# server.net
KiCad netlist of a schematic drawn in EAGLE
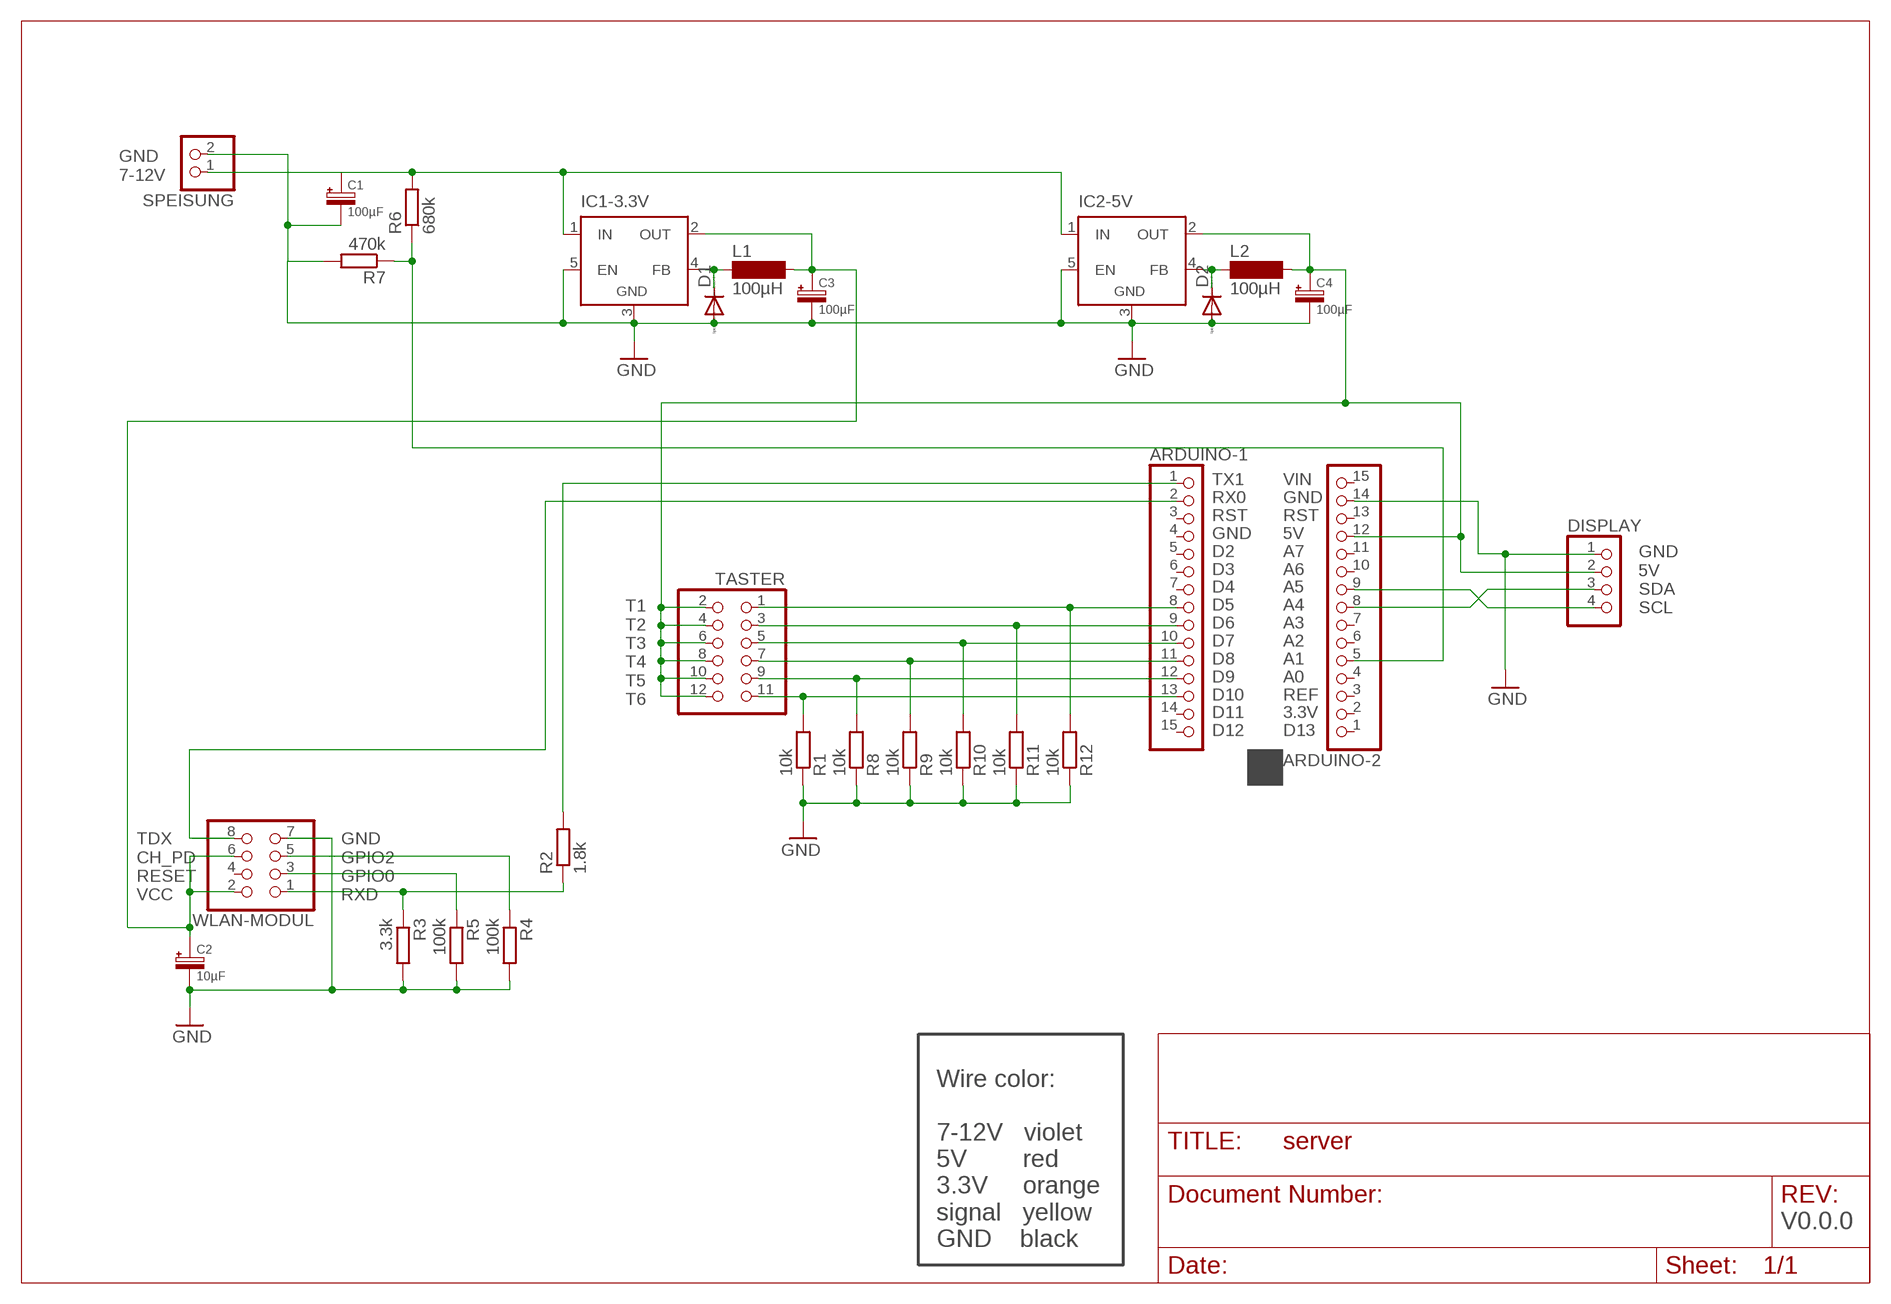
[diagram p0: schematic, sheet 1]

(export (version "E")
  (design (tool "Eeschema 10.0.6"))
  (components
    (comp (ref "ARDUINO-1")
      (value "PINHD-1X15")
      (footprint "eagle-import:1X15")
      (libsource (lib "eagle-import") (part "PINHD-1X15"))
    )
    (comp (ref "ARDUINO-2")
      (value "PINHD-1X15")
      (footprint "eagle-import:1X15")
      (libsource (lib "eagle-import") (part "PINHD-1X15"))
    )
    (comp (ref "C1")
      (value "100µF")
      (footprint "eagle-import:KONDENSATOR_ELEKTROLYT")
      (libsource (lib "eagle-import") (part "KONDENSATOR_ELEKTROLYT"))
    )
    (comp (ref "C2")
      (value "10µF")
      (footprint "eagle-import:KONDENSATOR_ELEKTROLYT")
      (libsource (lib "eagle-import") (part "KONDENSATOR_ELEKTROLYT"))
    )
    (comp (ref "C3")
      (value "100µF")
      (footprint "eagle-import:KONDENSATOR_ELEKTROLYT")
      (libsource (lib "eagle-import") (part "KONDENSATOR_ELEKTROLYT"))
    )
    (comp (ref "C4")
      (value "100µF")
      (footprint "eagle-import:KONDENSATOR_ELEKTROLYT")
      (libsource (lib "eagle-import") (part "KONDENSATOR_ELEKTROLYT"))
    )
    (comp (ref "D1")
      (value "DIODE-D-2.5")
      (footprint "eagle-import:D-2.5")
      (libsource (lib "eagle-import") (part "DIODE-D-2.5"))
    )
    (comp (ref "D2")
      (value "DIODE-D-2.5")
      (footprint "eagle-import:D-2.5")
      (libsource (lib "eagle-import") (part "DIODE-D-2.5"))
    )
    (comp (ref "DISPLAY")
      (value "PINHD-1X4")
      (footprint "eagle-import:1X04")
      (libsource (lib "eagle-import") (part "PINHD-1X4"))
    )
    (comp (ref "IC1-3.3V")
      (value "LM2596TV")
      (footprint "eagle-import:TO220-51")
      (libsource (lib "eagle-import") (part "LM2596TV"))
    )
    (comp (ref "IC2-5V")
      (value "LM2596TV")
      (footprint "eagle-import:TO220-51")
      (libsource (lib "eagle-import") (part "LM2596TV"))
    )
    (comp (ref "L1")
      (value "100µH")
      (footprint "eagle-import:SM-L15A")
      (libsource (lib "eagle-import") (part "SM-L15A"))
    )
    (comp (ref "L2")
      (value "100µH")
      (footprint "eagle-import:SM-L15A")
      (libsource (lib "eagle-import") (part "SM-L15A"))
    )
    (comp (ref "R1")
      (value "10k")
      (footprint "eagle-import:0207_15")
      (libsource (lib "eagle-import") (part "rcl_334_R-EU_0207/15"))
    )
    (comp (ref "R2")
      (value "1.8k")
      (footprint "eagle-import:0207_10")
      (libsource (lib "eagle-import") (part "R-EU_0207/10"))
    )
    (comp (ref "R3")
      (value "3.3k")
      (footprint "eagle-import:0207_10")
      (libsource (lib "eagle-import") (part "R-EU_0207/10"))
    )
    (comp (ref "R4")
      (value "100k")
      (footprint "eagle-import:0207_10")
      (libsource (lib "eagle-import") (part "R-EU_0207/10"))
    )
    (comp (ref "R5")
      (value "100k")
      (footprint "eagle-import:0207_10")
      (libsource (lib "eagle-import") (part "R-EU_0207/10"))
    )
    (comp (ref "R6")
      (value "680k")
      (footprint "eagle-import:0204V")
      (libsource (lib "eagle-import") (part "rcl_334_R-EU_0204/2V"))
    )
    (comp (ref "R7")
      (value "470k")
      (footprint "eagle-import:0204V")
      (libsource (lib "eagle-import") (part "rcl_334_R-EU_0204/2V"))
    )
    (comp (ref "R8")
      (value "10k")
      (footprint "eagle-import:0207_12")
      (libsource (lib "eagle-import") (part "rcl_334_R-EU_0207/12"))
    )
    (comp (ref "R9")
      (value "10k")
      (footprint "eagle-import:0207_10")
      (libsource (lib "eagle-import") (part "rcl_334_R-EU_0207/10"))
    )
    (comp (ref "R10")
      (value "10k")
      (footprint "eagle-import:0207_7")
      (libsource (lib "eagle-import") (part "rcl_334_R-EU_0207/7"))
    )
    (comp (ref "R11")
      (value "10k")
      (footprint "eagle-import:0207_5V")
      (libsource (lib "eagle-import") (part "rcl_334_R-EU_0207/5V"))
    )
    (comp (ref "R12")
      (value "10k")
      (footprint "eagle-import:0207_2V")
      (libsource (lib "eagle-import") (part "rcl_334_R-EU_0207/2V"))
    )
    (comp (ref "SPEISUNG")
      (value "PINHD-1X2")
      (footprint "eagle-import:1X02")
      (libsource (lib "eagle-import") (part "PINHD-1X2"))
    )
    (comp (ref "TASTER")
      (value "PINHD-2X6")
      (footprint "eagle-import:2X06")
      (libsource (lib "eagle-import") (part "PINHD-2X6"))
    )
    (comp (ref "WLAN-MODUL")
      (value "PINHD-2X4")
      (footprint "eagle-import:2X04")
      (libsource (lib "eagle-import") (part "PINHD-2X4"))
    )
  )
  (nets
    (net (code "1") (name "GND") (class "Default")
      (node (ref "ARDUINO-2") (pin "14") (pinfunction "14_14") (pintype "passive"))
      (node (ref "C1") (pin "P$1") (pinfunction "P$1_P$1") (pintype "passive"))
      (node (ref "C2") (pin "P$1") (pinfunction "P$1_P$1") (pintype "passive"))
      (node (ref "C3") (pin "P$1") (pinfunction "P$1_P$1") (pintype "passive"))
      (node (ref "C4") (pin "P$1") (pinfunction "P$1_P$1") (pintype "passive"))
      (node (ref "D1") (pin "A") (pinfunction "A_A") (pintype "passive"))
      (node (ref "D2") (pin "A") (pinfunction "A_A") (pintype "passive"))
      (node (ref "DISPLAY") (pin "1") (pinfunction "1_1") (pintype "passive"))
      (node (ref "IC1-3.3V") (pin "3") (pinfunction "GND_3") (pintype "power_in"))
      (node (ref "IC1-3.3V") (pin "5") (pinfunction "EN_5") (pintype "input"))
      (node (ref "IC2-5V") (pin "3") (pinfunction "GND_3") (pintype "power_in"))
      (node (ref "IC2-5V") (pin "5") (pinfunction "EN_5") (pintype "input"))
      (node (ref "R1") (pin "1") (pinfunction "1_1") (pintype "passive"))
      (node (ref "R10") (pin "1") (pinfunction "1_1") (pintype "passive"))
      (node (ref "R11") (pin "1") (pinfunction "1_1") (pintype "passive"))
      (node (ref "R12") (pin "1") (pinfunction "1_1") (pintype "passive"))
      (node (ref "R3") (pin "2") (pinfunction "2_2") (pintype "passive"))
      (node (ref "R4") (pin "2") (pinfunction "2_2") (pintype "passive"))
      (node (ref "R5") (pin "2") (pinfunction "2_2") (pintype "passive"))
      (node (ref "R7") (pin "2") (pinfunction "2_2") (pintype "passive"))
      (node (ref "R8") (pin "1") (pinfunction "1_1") (pintype "passive"))
      (node (ref "R9") (pin "1") (pinfunction "1_1") (pintype "passive"))
      (node (ref "SPEISUNG") (pin "2") (pinfunction "2_2") (pintype "passive"))
      (node (ref "WLAN-MODUL") (pin "7") (pinfunction "7_7") (pintype "passive"))
    )
    (net (code "2") (name "Net-(ARDUINO-1-Pad1)") (class "Default")
      (node (ref "ARDUINO-1") (pin "1") (pinfunction "1_1") (pintype "passive"))
      (node (ref "R2") (pin "2") (pinfunction "2_2") (pintype "passive"))
    )
    (net (code "3") (name "Net-(ARDUINO-1-Pad2)") (class "Default")
      (node (ref "ARDUINO-1") (pin "2") (pinfunction "2_2") (pintype "passive"))
      (node (ref "WLAN-MODUL") (pin "8") (pinfunction "8_8") (pintype "passive"))
    )
    (net (code "4") (name "Net-(ARDUINO-1-Pad8)") (class "Default")
      (node (ref "ARDUINO-1") (pin "8") (pinfunction "8_8") (pintype "passive"))
      (node (ref "R12") (pin "2") (pinfunction "2_2") (pintype "passive"))
      (node (ref "TASTER") (pin "1") (pinfunction "1_1") (pintype "passive"))
    )
    (net (code "5") (name "Net-(ARDUINO-1-Pad9)") (class "Default")
      (node (ref "ARDUINO-1") (pin "9") (pinfunction "9_9") (pintype "passive"))
      (node (ref "R11") (pin "2") (pinfunction "2_2") (pintype "passive"))
      (node (ref "TASTER") (pin "3") (pinfunction "3_3") (pintype "passive"))
    )
    (net (code "6") (name "Net-(ARDUINO-1-Pad10)") (class "Default")
      (node (ref "ARDUINO-1") (pin "10") (pinfunction "10_10") (pintype "passive"))
      (node (ref "R10") (pin "2") (pinfunction "2_2") (pintype "passive"))
      (node (ref "TASTER") (pin "5") (pinfunction "5_5") (pintype "passive"))
    )
    (net (code "7") (name "Net-(ARDUINO-1-Pad11)") (class "Default")
      (node (ref "ARDUINO-1") (pin "11") (pinfunction "11_11") (pintype "passive"))
      (node (ref "R9") (pin "2") (pinfunction "2_2") (pintype "passive"))
      (node (ref "TASTER") (pin "7") (pinfunction "7_7") (pintype "passive"))
    )
    (net (code "8") (name "Net-(ARDUINO-1-Pad12)") (class "Default")
      (node (ref "ARDUINO-1") (pin "12") (pinfunction "12_12") (pintype "passive"))
      (node (ref "R8") (pin "2") (pinfunction "2_2") (pintype "passive"))
      (node (ref "TASTER") (pin "9") (pinfunction "9_9") (pintype "passive"))
    )
    (net (code "9") (name "Net-(ARDUINO-1-Pad13)") (class "Default")
      (node (ref "ARDUINO-1") (pin "13") (pinfunction "13_13") (pintype "passive"))
      (node (ref "R1") (pin "2") (pinfunction "2_2") (pintype "passive"))
      (node (ref "TASTER") (pin "11") (pinfunction "11_11") (pintype "passive"))
    )
    (net (code "10") (name "Net-(ARDUINO-2-Pad5)") (class "Default")
      (node (ref "ARDUINO-2") (pin "5") (pinfunction "5_5") (pintype "passive"))
      (node (ref "R6") (pin "1") (pinfunction "1_1") (pintype "passive"))
      (node (ref "R7") (pin "1") (pinfunction "1_1") (pintype "passive"))
    )
    (net (code "11") (name "Net-(ARDUINO-2-Pad8)") (class "Default")
      (node (ref "ARDUINO-2") (pin "8") (pinfunction "8_8") (pintype "passive"))
      (node (ref "DISPLAY") (pin "3") (pinfunction "3_3") (pintype "passive"))
    )
    (net (code "12") (name "Net-(ARDUINO-2-Pad9)") (class "Default")
      (node (ref "ARDUINO-2") (pin "9") (pinfunction "9_9") (pintype "passive"))
      (node (ref "DISPLAY") (pin "4") (pinfunction "4_4") (pintype "passive"))
    )
    (net (code "13") (name "Net-(IC1-3.3V-FB)") (class "Default")
      (node (ref "D1") (pin "C") (pinfunction "C_C") (pintype "passive"))
      (node (ref "IC1-3.3V") (pin "4") (pinfunction "FB_4") (pintype "input"))
      (node (ref "L1") (pin "1") (pinfunction "1_1") (pintype "passive"))
    )
    (net (code "14") (name "Net-(IC1-3.3V-IN)") (class "Default")
      (node (ref "C1") (pin "P$2") (pinfunction "P$2_P$2") (pintype "passive"))
      (node (ref "IC1-3.3V") (pin "1") (pinfunction "IN_1") (pintype "input"))
      (node (ref "IC2-5V") (pin "1") (pinfunction "IN_1") (pintype "input"))
      (node (ref "R6") (pin "2") (pinfunction "2_2") (pintype "passive"))
      (node (ref "SPEISUNG") (pin "1") (pinfunction "1_1") (pintype "passive"))
    )
    (net (code "15") (name "Net-(IC1-3.3V-OUT)") (class "Default")
      (node (ref "C2") (pin "P$2") (pinfunction "P$2_P$2") (pintype "passive"))
      (node (ref "C3") (pin "P$2") (pinfunction "P$2_P$2") (pintype "passive"))
      (node (ref "IC1-3.3V") (pin "2") (pinfunction "OUT_2") (pintype "output"))
      (node (ref "L1") (pin "2") (pinfunction "2_2") (pintype "passive"))
      (node (ref "WLAN-MODUL") (pin "2") (pinfunction "2_2") (pintype "passive"))
      (node (ref "WLAN-MODUL") (pin "6") (pinfunction "6_6") (pintype "passive"))
    )
    (net (code "16") (name "Net-(IC2-5V-FB)") (class "Default")
      (node (ref "D2") (pin "C") (pinfunction "C_C") (pintype "passive"))
      (node (ref "IC2-5V") (pin "4") (pinfunction "FB_4") (pintype "input"))
      (node (ref "L2") (pin "1") (pinfunction "1_1") (pintype "passive"))
    )
    (net (code "17") (name "Net-(IC2-5V-OUT)") (class "Default")
      (node (ref "ARDUINO-2") (pin "12") (pinfunction "12_12") (pintype "passive"))
      (node (ref "C4") (pin "P$2") (pinfunction "P$2_P$2") (pintype "passive"))
      (node (ref "DISPLAY") (pin "2") (pinfunction "2_2") (pintype "passive"))
      (node (ref "IC2-5V") (pin "2") (pinfunction "OUT_2") (pintype "output"))
      (node (ref "L2") (pin "2") (pinfunction "2_2") (pintype "passive"))
      (node (ref "TASTER") (pin "10") (pinfunction "10_10") (pintype "passive"))
      (node (ref "TASTER") (pin "12") (pinfunction "12_12") (pintype "passive"))
      (node (ref "TASTER") (pin "2") (pinfunction "2_2") (pintype "passive"))
      (node (ref "TASTER") (pin "4") (pinfunction "4_4") (pintype "passive"))
      (node (ref "TASTER") (pin "6") (pinfunction "6_6") (pintype "passive"))
      (node (ref "TASTER") (pin "8") (pinfunction "8_8") (pintype "passive"))
    )
    (net (code "18") (name "Net-(R2-Pad1)") (class "Default")
      (node (ref "R2") (pin "1") (pinfunction "1_1") (pintype "passive"))
      (node (ref "R3") (pin "1") (pinfunction "1_1") (pintype "passive"))
      (node (ref "WLAN-MODUL") (pin "1") (pinfunction "1_1") (pintype "passive"))
    )
    (net (code "19") (name "Net-(R4-Pad1)") (class "Default")
      (node (ref "R4") (pin "1") (pinfunction "1_1") (pintype "passive"))
      (node (ref "WLAN-MODUL") (pin "5") (pinfunction "5_5") (pintype "passive"))
    )
    (net (code "20") (name "Net-(R5-Pad1)") (class "Default")
      (node (ref "R5") (pin "1") (pinfunction "1_1") (pintype "passive"))
      (node (ref "WLAN-MODUL") (pin "3") (pinfunction "3_3") (pintype "passive"))
    )
    (net (code "21") (name "unconnected-(ARDUINO-1-Pad3)") (class "Default")
      (node (ref "ARDUINO-1") (pin "3") (pinfunction "3_3") (pintype "passive"))
    )
    (net (code "22") (name "unconnected-(ARDUINO-1-Pad4)") (class "Default")
      (node (ref "ARDUINO-1") (pin "4") (pinfunction "4_4") (pintype "passive"))
    )
    (net (code "23") (name "unconnected-(ARDUINO-1-Pad5)") (class "Default")
      (node (ref "ARDUINO-1") (pin "5") (pinfunction "5_5") (pintype "passive"))
    )
    (net (code "24") (name "unconnected-(ARDUINO-1-Pad6)") (class "Default")
      (node (ref "ARDUINO-1") (pin "6") (pinfunction "6_6") (pintype "passive"))
    )
    (net (code "25") (name "unconnected-(ARDUINO-1-Pad7)") (class "Default")
      (node (ref "ARDUINO-1") (pin "7") (pinfunction "7_7") (pintype "passive"))
    )
    (net (code "26") (name "unconnected-(ARDUINO-1-Pad14)") (class "Default")
      (node (ref "ARDUINO-1") (pin "14") (pinfunction "14_14") (pintype "passive"))
    )
    (net (code "27") (name "unconnected-(ARDUINO-1-Pad15)") (class "Default")
      (node (ref "ARDUINO-1") (pin "15") (pinfunction "15_15") (pintype "passive"))
    )
    (net (code "28") (name "unconnected-(ARDUINO-2-Pad1)") (class "Default")
      (node (ref "ARDUINO-2") (pin "1") (pinfunction "1_1") (pintype "passive"))
    )
    (net (code "29") (name "unconnected-(ARDUINO-2-Pad2)") (class "Default")
      (node (ref "ARDUINO-2") (pin "2") (pinfunction "2_2") (pintype "passive"))
    )
    (net (code "30") (name "unconnected-(ARDUINO-2-Pad3)") (class "Default")
      (node (ref "ARDUINO-2") (pin "3") (pinfunction "3_3") (pintype "passive"))
    )
    (net (code "31") (name "unconnected-(ARDUINO-2-Pad4)") (class "Default")
      (node (ref "ARDUINO-2") (pin "4") (pinfunction "4_4") (pintype "passive"))
    )
    (net (code "32") (name "unconnected-(ARDUINO-2-Pad6)") (class "Default")
      (node (ref "ARDUINO-2") (pin "6") (pinfunction "6_6") (pintype "passive"))
    )
    (net (code "33") (name "unconnected-(ARDUINO-2-Pad7)") (class "Default")
      (node (ref "ARDUINO-2") (pin "7") (pinfunction "7_7") (pintype "passive"))
    )
    (net (code "34") (name "unconnected-(ARDUINO-2-Pad10)") (class "Default")
      (node (ref "ARDUINO-2") (pin "10") (pinfunction "10_10") (pintype "passive"))
    )
    (net (code "35") (name "unconnected-(ARDUINO-2-Pad11)") (class "Default")
      (node (ref "ARDUINO-2") (pin "11") (pinfunction "11_11") (pintype "passive"))
    )
    (net (code "36") (name "unconnected-(ARDUINO-2-Pad13)") (class "Default")
      (node (ref "ARDUINO-2") (pin "13") (pinfunction "13_13") (pintype "passive"))
    )
    (net (code "37") (name "unconnected-(ARDUINO-2-Pad15)") (class "Default")
      (node (ref "ARDUINO-2") (pin "15") (pinfunction "15_15") (pintype "passive"))
    )
    (net (code "38") (name "unconnected-(WLAN-MODUL-Pad4)") (class "Default")
      (node (ref "WLAN-MODUL") (pin "4") (pinfunction "4_4") (pintype "passive"))
    )
  )
)
